# untitled.net
KiCad netlist of a schematic drawn in EAGLE
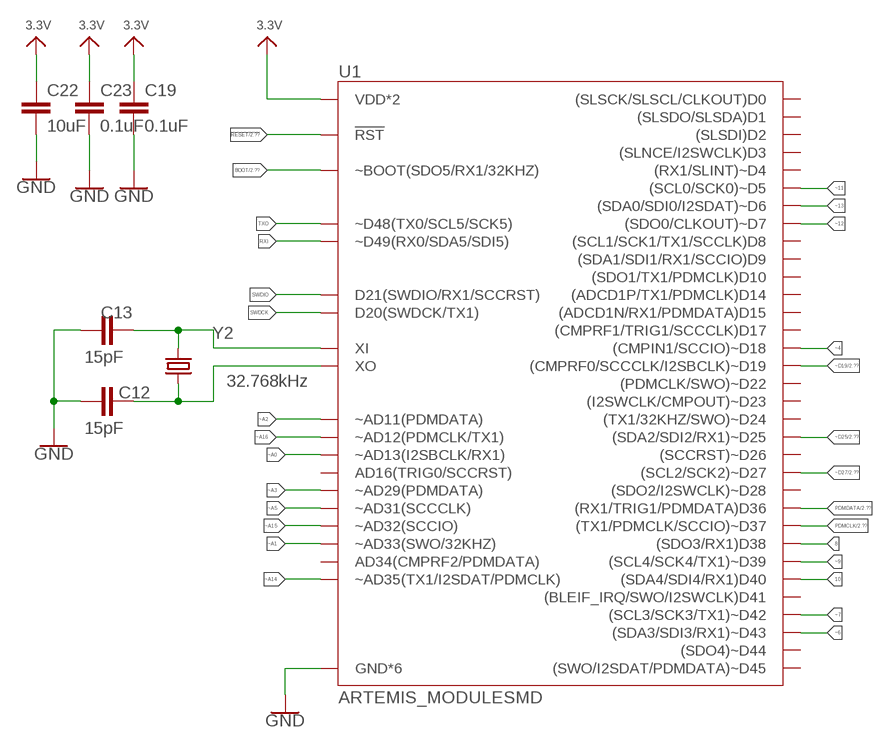
[diagram p0: schematic, sheet 1, part 1 of 2]
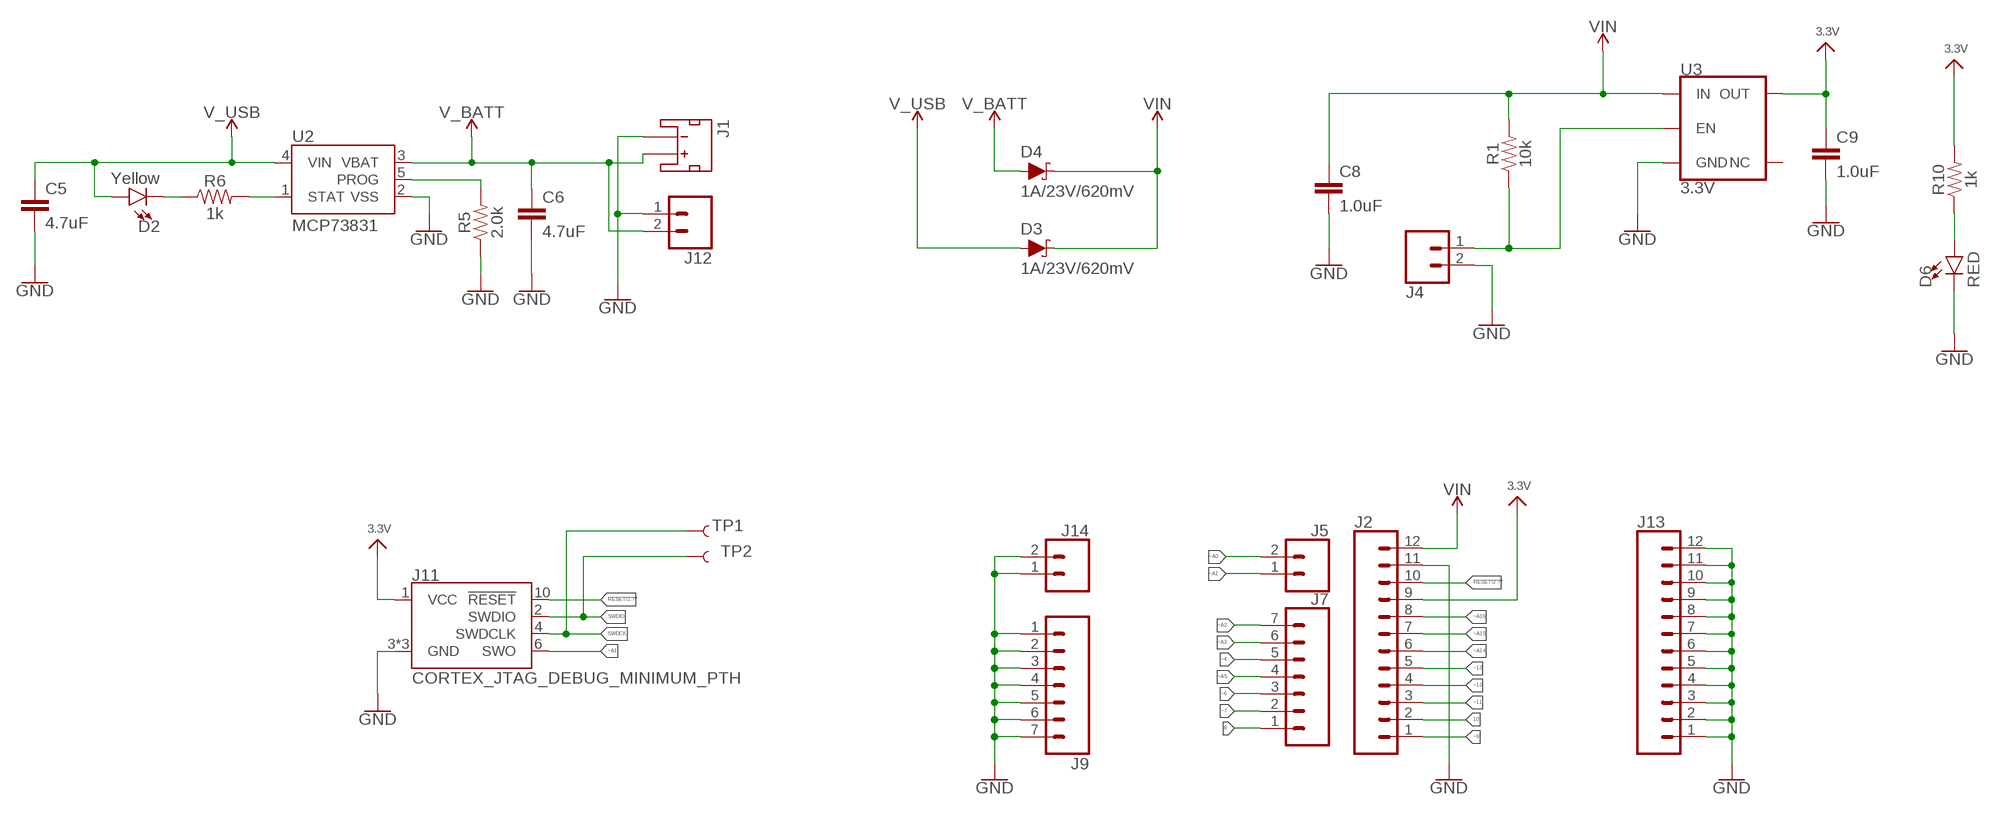
[diagram p1: schematic, sheet 1, part 2 of 2]
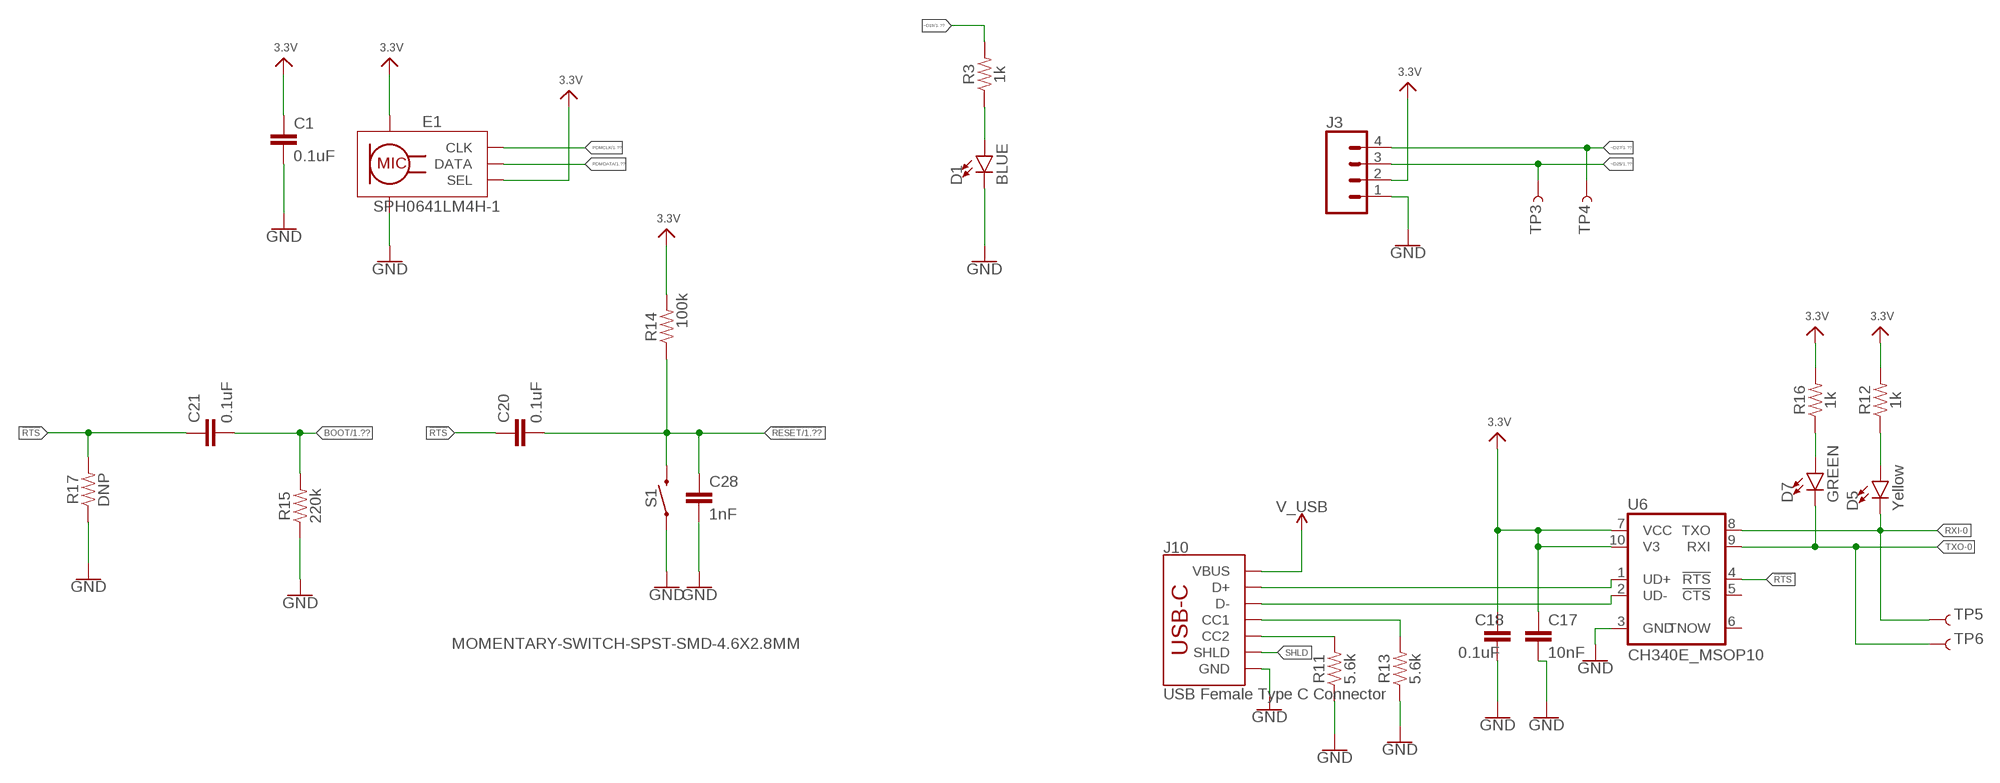
[diagram p2: schematic, sheet 2]

(export (version "E")
  (design (tool "Eeschema 10.0.6"))
  (components
    (comp (ref "C5")
      (value "4.7uF")
      (footprint "eagle-import:0603")
      (libsource (lib "eagle-import") (part "4.7UF-0603-6.3V-(10%)"))
    )
    (comp (ref "C6")
      (value "4.7uF")
      (footprint "eagle-import:0603")
      (libsource (lib "eagle-import") (part "4.7UF-0603-6.3V-(10%)"))
    )
    (comp (ref "C8")
      (value "1.0uF")
      (footprint "eagle-import:0402-TIGHT")
      (libsource (lib "eagle-import") (part "1.0UF-0402T-16V-10%"))
    )
    (comp (ref "C9")
      (value "1.0uF")
      (footprint "eagle-import:0402-TIGHT")
      (libsource (lib "eagle-import") (part "1.0UF-0402T-16V-10%"))
    )
    (comp (ref "C12")
      (value "15pF")
      (footprint "eagle-import:0603")
      (libsource (lib "eagle-import") (part "15PF-0603-50V-5%"))
    )
    (comp (ref "C13")
      (value "15pF")
      (footprint "eagle-import:0603")
      (libsource (lib "eagle-import") (part "15PF-0603-50V-5%"))
    )
    (comp (ref "C19")
      (value "0.1uF")
      (footprint "eagle-import:0402-TIGHT")
      (libsource (lib "eagle-import") (part "0.1UF-0402T-16V-10%"))
    )
    (comp (ref "C22")
      (value "10uF")
      (footprint "eagle-import:0603")
      (libsource (lib "eagle-import") (part "10UF-0603-6.3V-20%"))
    )
    (comp (ref "C23")
      (value "0.1uF")
      (footprint "eagle-import:0402-TIGHT")
      (libsource (lib "eagle-import") (part "0.1UF-0402T-16V-10%"))
    )
    (comp (ref "D2")
      (value "Yellow")
      (footprint "eagle-import:LED-0603")
      (libsource (lib "eagle-import") (part "LED-YELLOW0603"))
    )
    (comp (ref "D3")
      (value "1A/23V/620mV")
      (footprint "eagle-import:SOD-323")
      (libsource (lib "eagle-import") (part "DIODE-SCHOTTKY-BAT20J"))
    )
    (comp (ref "D4")
      (value "1A/23V/620mV")
      (footprint "eagle-import:SOD-323")
      (libsource (lib "eagle-import") (part "DIODE-SCHOTTKY-BAT20J"))
    )
    (comp (ref "D6")
      (value "RED")
      (footprint "eagle-import:LED-0603")
      (libsource (lib "eagle-import") (part "LED-RED0603"))
    )
    (comp (ref "J1")
      (value "JST_2MM_MALE")
      (footprint "eagle-import:JST-2-SMD")
      (libsource (lib "eagle-import") (part "JST_2MM_MALE"))
    )
    (comp (ref "J2")
      (value "CONN_12NO_SILK")
      (footprint "eagle-import:1X12_NO_SILK")
      (libsource (lib "eagle-import") (part "CONN_12NO_SILK"))
    )
    (comp (ref "J4")
      (value "CONN_021X02_NO_SILK")
      (footprint "eagle-import:1X02_NO_SILK")
      (libsource (lib "eagle-import") (part "CONN_021X02_NO_SILK"))
    )
    (comp (ref "J5")
      (value "CONN_021X02_NO_SILK")
      (footprint "eagle-import:1X02_NO_SILK")
      (libsource (lib "eagle-import") (part "CONN_021X02_NO_SILK"))
    )
    (comp (ref "J7")
      (value "CONN_07NO_SILK")
      (footprint "eagle-import:1X07_NO_SILK")
      (libsource (lib "eagle-import") (part "CONN_07NO_SILK"))
    )
    (comp (ref "J9")
      (value "CONN_07NO_SILK")
      (footprint "eagle-import:1X07_NO_SILK")
      (libsource (lib "eagle-import") (part "CONN_07NO_SILK"))
    )
    (comp (ref "J11")
      (value "CORTEX_JTAG_DEBUG_MINIMUM_PTH")
      (footprint "eagle-import:2X5-PTH-1.27MM")
      (libsource (lib "eagle-import") (part "CORTEX_JTAG_DEBUG_MINIMUM_PTH"))
    )
    (comp (ref "J12")
      (value "CONN_021X02_NO_SILK")
      (footprint "eagle-import:1X02_NO_SILK")
      (libsource (lib "eagle-import") (part "CONN_021X02_NO_SILK"))
    )
    (comp (ref "J13")
      (value "CONN_12NO_SILK")
      (footprint "eagle-import:1X12_NO_SILK")
      (libsource (lib "eagle-import") (part "CONN_12NO_SILK"))
    )
    (comp (ref "J14")
      (value "CONN_021X02_NO_SILK")
      (footprint "eagle-import:1X02_NO_SILK")
      (libsource (lib "eagle-import") (part "CONN_021X02_NO_SILK"))
    )
    (comp (ref "R1")
      (value "10k")
      (footprint "eagle-import:0603")
      (libsource (lib "eagle-import") (part "10KOHM-0603-1/10W-1%"))
    )
    (comp (ref "R5")
      (value "2.0k")
      (footprint "eagle-import:0603")
      (libsource (lib "eagle-import") (part "2.0KOHM-0603-1/10W-5%"))
    )
    (comp (ref "R6")
      (value "1k")
      (footprint "eagle-import:0603")
      (libsource (lib "eagle-import") (part "1KOHM-0603-1/10W-1%"))
    )
    (comp (ref "R10")
      (value "1k")
      (footprint "eagle-import:0603")
      (libsource (lib "eagle-import") (part "1KOHM-0603-1/10W-1%"))
    )
    (comp (ref "TP1")
      (value "TEST-POINT3X5")
      (footprint "eagle-import:PAD.03X.05")
      (libsource (lib "eagle-import") (part "TEST-POINT3X5"))
    )
    (comp (ref "TP2")
      (value "TEST-POINT3X5")
      (footprint "eagle-import:PAD.03X.05")
      (libsource (lib "eagle-import") (part "TEST-POINT3X5"))
    )
    (comp (ref "U1")
      (value "ARTEMIS_MODULESMD")
      (footprint "eagle-import:ARTEMIS_FP")
      (libsource (lib "eagle-import") (part "ARTEMIS_MODULESMD"))
    )
    (comp (ref "U2")
      (value "MCP73831")
      (footprint "eagle-import:SOT23-5")
      (libsource (lib "eagle-import") (part "MCP73831"))
    )
    (comp (ref "U3")
      (value "3.3V")
      (footprint "eagle-import:SOT23-5")
      (libsource (lib "eagle-import") (part "V_REG_AP2112K-3.3V"))
    )
    (comp (ref "Y2")
      (value "32.768kHz")
      (footprint "eagle-import:CRYSTAL-SMD-3.2X1.5MM")
      (libsource (lib "eagle-import") (part "CRYSTAL-32.768KHZSMD-3.2X1.5"))
    )
    (comp (ref "C1")
      (value "0.1uF")
      (footprint "eagle-import:0402-TIGHT")
      (libsource (lib "eagle-import") (part "0.1UF-0402T-16V-10%"))
    )
    (comp (ref "C17")
      (value "10nF")
      (footprint "eagle-import:0603")
      (libsource (lib "eagle-import") (part "10NF-0603-50V-10%"))
    )
    (comp (ref "C18")
      (value "0.1uF")
      (footprint "eagle-import:0603")
      (libsource (lib "eagle-import") (part "0.1UF-0603-25V-(+80/-20%)"))
    )
    (comp (ref "C20")
      (value "0.1uF")
      (footprint "eagle-import:0603")
      (libsource (lib "eagle-import") (part "0.1UF-0603-25V-5%"))
    )
    (comp (ref "C21")
      (value "0.1uF")
      (footprint "eagle-import:0603")
      (libsource (lib "eagle-import") (part "0.1UF-0603-25V-5%"))
    )
    (comp (ref "C28")
      (value "1nF")
      (footprint "eagle-import:0603")
      (libsource (lib "eagle-import") (part "1.0NF/1000PF-0603-50V-10%"))
    )
    (comp (ref "D1")
      (value "BLUE")
      (footprint "eagle-import:LED-0603")
      (libsource (lib "eagle-import") (part "LED-BLUE0603"))
    )
    (comp (ref "D5")
      (value "Yellow")
      (footprint "eagle-import:LED-0603")
      (libsource (lib "eagle-import") (part "LED-YELLOW0603"))
    )
    (comp (ref "D7")
      (value "GREEN")
      (footprint "eagle-import:LED-0603")
      (libsource (lib "eagle-import") (part "LED-GREEN0603"))
    )
    (comp (ref "E1")
      (value "SPH0641LM4H-1")
      (footprint "eagle-import:SPH0641LM4H-1_MICROPHONE")
      (libsource (lib "eagle-import") (part "SPH0641LM4H-1_MICROPHONE"))
    )
    (comp (ref "J3")
      (value "CONN_04SMD2")
      (footprint "eagle-import:JST04_1MM_RA")
      (libsource (lib "eagle-import") (part "CONN_04SMD2"))
    )
    (comp (ref "J10")
      (value "USB Female Type C Connector")
      (footprint "eagle-import:USB-C-16P-4LAYER-ISOLATED")
      (libsource (lib "eagle-import") (part "USB_C_4-LAYER-ISOLATED"))
    )
    (comp (ref "R3")
      (value "1k")
      (footprint "eagle-import:0603")
      (libsource (lib "eagle-import") (part "1KOHM-0603-1/10W-1%"))
    )
    (comp (ref "R11")
      (value "5.6k")
      (footprint "eagle-import:0603")
      (libsource (lib "eagle-import") (part "5.6KOHM-0603-1/10W-1%"))
    )
    (comp (ref "R12")
      (value "1k")
      (footprint "eagle-import:0603")
      (libsource (lib "eagle-import") (part "1KOHM-0603-1/10W-1%"))
    )
    (comp (ref "R13")
      (value "5.6k")
      (footprint "eagle-import:0603")
      (libsource (lib "eagle-import") (part "5.6KOHM-0603-1/10W-1%"))
    )
    (comp (ref "R14")
      (value "100k")
      (footprint "eagle-import:0603")
      (libsource (lib "eagle-import") (part "100KOHM-0603-1/10W-1%"))
    )
    (comp (ref "R15")
      (value "220k")
      (footprint "eagle-import:0603")
      (libsource (lib "eagle-import") (part "220KOHM-0603-1/10W-1%"))
    )
    (comp (ref "R16")
      (value "1k")
      (footprint "eagle-import:0603")
      (libsource (lib "eagle-import") (part "1KOHM-0603-1/10W-1%"))
    )
    (comp (ref "R17")
      (value "DNP")
      (footprint "eagle-import:0603")
      (libsource (lib "eagle-import") (part "DNP-0603"))
    )
    (comp (ref "S1")
      (value "MOMENTARY-SWITCH-SPST-SMD-4.6X2.8MM")
      (footprint "eagle-import:TACTILE_SWITCH_SMD_4.6X2.8MM")
      (libsource (lib "eagle-import") (part "MOMENTARY-SWITCH-SPST-SMD-4.6X2.8MM"))
    )
    (comp (ref "TP3")
      (value "TEST-POINT3X5")
      (footprint "eagle-import:PAD.03X.05")
      (libsource (lib "eagle-import") (part "TEST-POINT3X5"))
    )
    (comp (ref "TP4")
      (value "TEST-POINT3X5")
      (footprint "eagle-import:PAD.03X.05")
      (libsource (lib "eagle-import") (part "TEST-POINT3X5"))
    )
    (comp (ref "TP5")
      (value "TEST-POINT3X5")
      (footprint "eagle-import:PAD.03X.05")
      (libsource (lib "eagle-import") (part "TEST-POINT3X5"))
    )
    (comp (ref "TP6")
      (value "TEST-POINT3X5")
      (footprint "eagle-import:PAD.03X.05")
      (libsource (lib "eagle-import") (part "TEST-POINT3X5"))
    )
    (comp (ref "U6")
      (value "CH340E_MSOP10")
      (footprint "eagle-import:MSOP10")
      (libsource (lib "eagle-import") (part "CH340E_MSOP10"))
    )
  )
  (nets
    (net (code "1") (name "3.3V") (class "Default")
      (node (ref "C1") (pin "1") (pinfunction "1_1") (pintype "passive"))
      (node (ref "C17") (pin "1") (pinfunction "1_1") (pintype "passive"))
      (node (ref "C18") (pin "1") (pinfunction "1_1") (pintype "passive"))
      (node (ref "C19") (pin "1") (pinfunction "1_1") (pintype "passive"))
      (node (ref "C22") (pin "1") (pinfunction "1_1") (pintype "passive"))
      (node (ref "C23") (pin "1") (pinfunction "1_1") (pintype "passive"))
      (node (ref "C9") (pin "1") (pinfunction "1_1") (pintype "passive"))
      (node (ref "E1") (pin "2") (pinfunction "SEL_2") (pintype "input"))
      (node (ref "E1") (pin "5") (pinfunction "VDD_5") (pintype "power_in"))
      (node (ref "J11") (pin "1") (pinfunction "VCC_1") (pintype "bidirectional"))
      (node (ref "J2") (pin "9") (pinfunction "9_9") (pintype "passive"))
      (node (ref "J3") (pin "2") (pinfunction "2_2") (pintype "passive"))
      (node (ref "R10") (pin "2") (pinfunction "2_2") (pintype "passive"))
      (node (ref "R12") (pin "2") (pinfunction "2_2") (pintype "passive"))
      (node (ref "R14") (pin "2") (pinfunction "2_2") (pintype "passive"))
      (node (ref "R16") (pin "2") (pinfunction "2_2") (pintype "passive"))
      (node (ref "U1") (pin "VDD@36") (pinfunction "VDD*2_VDD@36") (pintype "bidirectional"))
      (node (ref "U1") (pin "VDD@37") (pinfunction "VDD*2_VDD@37") (pintype "bidirectional"))
      (node (ref "U3") (pin "5") (pinfunction "OUT_5") (pintype "passive"))
      (node (ref "U6") (pin "10") (pinfunction "V3_10") (pintype "bidirectional"))
      (node (ref "U6") (pin "7") (pinfunction "VCC_7") (pintype "bidirectional"))
    )
    (net (code "2") (name "8") (class "Default")
      (node (ref "J7") (pin "1") (pinfunction "1_1") (pintype "passive"))
      (node (ref "U1") (pin "D38") (pinfunction "(SDO3/RX1)D38_D38") (pintype "bidirectional"))
    )
    (net (code "3") (name "10") (class "Default")
      (node (ref "J2") (pin "2") (pinfunction "2_2") (pintype "passive"))
      (node (ref "U1") (pin "D40") (pinfunction "(SDA4/SDI4/RX1)D40_D40") (pintype "bidirectional"))
    )
    (net (code "4") (name "BOOT") (class "Default")
      (node (ref "C21") (pin "2") (pinfunction "2_2") (pintype "passive"))
      (node (ref "R15") (pin "2") (pinfunction "2_2") (pintype "passive"))
      (node (ref "U1") (pin "BOOT") (pinfunction "~{BOOT(SDO5/RX1/32KHZ})_BOOT") (pintype "bidirectional"))
    )
    (net (code "5") (name "GND") (class "Default")
      (node (ref "C1") (pin "2") (pinfunction "2_2") (pintype "passive"))
      (node (ref "C12") (pin "1") (pinfunction "1_1") (pintype "passive"))
      (node (ref "C13") (pin "1") (pinfunction "1_1") (pintype "passive"))
      (node (ref "C17") (pin "2") (pinfunction "2_2") (pintype "passive"))
      (node (ref "C18") (pin "2") (pinfunction "2_2") (pintype "passive"))
      (node (ref "C19") (pin "2") (pinfunction "2_2") (pintype "passive"))
      (node (ref "C22") (pin "2") (pinfunction "2_2") (pintype "passive"))
      (node (ref "C23") (pin "2") (pinfunction "2_2") (pintype "passive"))
      (node (ref "C28") (pin "2") (pinfunction "2_2") (pintype "passive"))
      (node (ref "C5") (pin "2") (pinfunction "2_2") (pintype "passive"))
      (node (ref "C6") (pin "2") (pinfunction "2_2") (pintype "passive"))
      (node (ref "C8") (pin "2") (pinfunction "2_2") (pintype "passive"))
      (node (ref "C9") (pin "2") (pinfunction "2_2") (pintype "passive"))
      (node (ref "D1") (pin "C") (pinfunction "C_C") (pintype "passive"))
      (node (ref "D6") (pin "C") (pinfunction "C_C") (pintype "passive"))
      (node (ref "E1") (pin "3") (pinfunction "GND_3") (pintype "power_in"))
      (node (ref "E1") (pin "6") (pinfunction "GND_6") (pintype "power_in"))
      (node (ref "E1") (pin "7") (pinfunction "GND_7") (pintype "power_in"))
      (node (ref "E1") (pin "8") (pinfunction "GND_8") (pintype "power_in"))
      (node (ref "J1") (pin "1") (pinfunction "-_1") (pintype "bidirectional"))
      (node (ref "J10") (pin "GND") (pinfunction "GND_GND") (pintype "bidirectional"))
      (node (ref "J10") (pin "GND2") (pinfunction "GND_GND2") (pintype "bidirectional"))
      (node (ref "J11") (pin "3") (pinfunction "GND_3") (pintype "bidirectional"))
      (node (ref "J11") (pin "5") (pinfunction "GND_5") (pintype "bidirectional"))
      (node (ref "J11") (pin "9") (pinfunction "GND_9") (pintype "bidirectional"))
      (node (ref "J12") (pin "1") (pinfunction "1_1") (pintype "passive"))
      (node (ref "J13") (pin "1") (pinfunction "1_1") (pintype "passive"))
      (node (ref "J13") (pin "10") (pinfunction "10_10") (pintype "passive"))
      (node (ref "J13") (pin "11") (pinfunction "11_11") (pintype "passive"))
      (node (ref "J13") (pin "12") (pinfunction "12_12") (pintype "passive"))
      (node (ref "J13") (pin "2") (pinfunction "2_2") (pintype "passive"))
      (node (ref "J13") (pin "3") (pinfunction "3_3") (pintype "passive"))
      (node (ref "J13") (pin "4") (pinfunction "4_4") (pintype "passive"))
      (node (ref "J13") (pin "5") (pinfunction "5_5") (pintype "passive"))
      (node (ref "J13") (pin "6") (pinfunction "6_6") (pintype "passive"))
      (node (ref "J13") (pin "7") (pinfunction "7_7") (pintype "passive"))
      (node (ref "J13") (pin "8") (pinfunction "8_8") (pintype "passive"))
      (node (ref "J13") (pin "9") (pinfunction "9_9") (pintype "passive"))
      (node (ref "J14") (pin "1") (pinfunction "1_1") (pintype "passive"))
      (node (ref "J14") (pin "2") (pinfunction "2_2") (pintype "passive"))
      (node (ref "J2") (pin "11") (pinfunction "11_11") (pintype "passive"))
      (node (ref "J3") (pin "1") (pinfunction "1_1") (pintype "passive"))
      (node (ref "J4") (pin "2") (pinfunction "2_2") (pintype "passive"))
      (node (ref "J9") (pin "1") (pinfunction "1_1") (pintype "passive"))
      (node (ref "J9") (pin "2") (pinfunction "2_2") (pintype "passive"))
      (node (ref "J9") (pin "3") (pinfunction "3_3") (pintype "passive"))
      (node (ref "J9") (pin "4") (pinfunction "4_4") (pintype "passive"))
      (node (ref "J9") (pin "5") (pinfunction "5_5") (pintype "passive"))
      (node (ref "J9") (pin "6") (pinfunction "6_6") (pintype "passive"))
      (node (ref "J9") (pin "7") (pinfunction "7_7") (pintype "passive"))
      (node (ref "R11") (pin "1") (pinfunction "1_1") (pintype "passive"))
      (node (ref "R13") (pin "1") (pinfunction "1_1") (pintype "passive"))
      (node (ref "R15") (pin "1") (pinfunction "1_1") (pintype "passive"))
      (node (ref "R17") (pin "1") (pinfunction "1_1") (pintype "passive"))
      (node (ref "R5") (pin "1") (pinfunction "1_1") (pintype "passive"))
      (node (ref "S1") (pin "1") (pinfunction "1_1") (pintype "passive"))
      (node (ref "S1") (pin "2") (pinfunction "1_2") (pintype "passive"))
      (node (ref "U1") (pin "GND@1") (pinfunction "GND*6_GND@1") (pintype "bidirectional"))
      (node (ref "U1") (pin "GND@22") (pinfunction "GND*6_GND@22") (pintype "bidirectional"))
      (node (ref "U1") (pin "GND@38") (pinfunction "GND*6_GND@38") (pintype "bidirectional"))
      (node (ref "U1") (pin "GND@39") (pinfunction "GND*6_GND@39") (pintype "bidirectional"))
      (node (ref "U1") (pin "GND@47") (pinfunction "GND*6_GND@47") (pintype "bidirectional"))
      (node (ref "U1") (pin "GND@59") (pinfunction "GND*6_GND@59") (pintype "bidirectional"))
      (node (ref "U2") (pin "2") (pinfunction "VSS_2") (pintype "power_in"))
      (node (ref "U3") (pin "2") (pinfunction "GND_2") (pintype "input"))
      (node (ref "U6") (pin "3") (pinfunction "GND_3") (pintype "bidirectional"))
    )
    (net (code "6") (name "Net-(D1-PadA)") (class "Default")
      (node (ref "D1") (pin "A") (pinfunction "A_A") (pintype "passive"))
      (node (ref "R3") (pin "1") (pinfunction "1_1") (pintype "passive"))
    )
    (net (code "7") (name "Net-(D2-PadC)") (class "Default")
      (node (ref "D2") (pin "C") (pinfunction "C_C") (pintype "passive"))
      (node (ref "R6") (pin "1") (pinfunction "1_1") (pintype "passive"))
    )
    (net (code "8") (name "Net-(D5-PadA)") (class "Default")
      (node (ref "D5") (pin "A") (pinfunction "A_A") (pintype "passive"))
      (node (ref "R12") (pin "1") (pinfunction "1_1") (pintype "passive"))
    )
    (net (code "9") (name "Net-(D6-PadA)") (class "Default")
      (node (ref "D6") (pin "A") (pinfunction "A_A") (pintype "passive"))
      (node (ref "R10") (pin "1") (pinfunction "1_1") (pintype "passive"))
    )
    (net (code "10") (name "Net-(D7-PadA)") (class "Default")
      (node (ref "D7") (pin "A") (pinfunction "A_A") (pintype "passive"))
      (node (ref "R16") (pin "1") (pinfunction "1_1") (pintype "passive"))
    )
    (net (code "11") (name "Net-(J10-CC1)") (class "Default")
      (node (ref "J10") (pin "A5") (pinfunction "CC1_A5") (pintype "bidirectional"))
      (node (ref "R13") (pin "2") (pinfunction "2_2") (pintype "passive"))
    )
    (net (code "12") (name "Net-(J10-CC2)") (class "Default")
      (node (ref "J10") (pin "B5") (pinfunction "CC2_B5") (pintype "bidirectional"))
      (node (ref "R11") (pin "2") (pinfunction "2_2") (pintype "passive"))
    )
    (net (code "13") (name "Net-(U2-PROG)") (class "Default")
      (node (ref "R5") (pin "2") (pinfunction "2_2") (pintype "passive"))
      (node (ref "U2") (pin "5") (pinfunction "PROG_5") (pintype "input"))
    )
    (net (code "14") (name "Net-(U2-STAT)") (class "Default")
      (node (ref "R6") (pin "2") (pinfunction "2_2") (pintype "passive"))
      (node (ref "U2") (pin "1") (pinfunction "STAT_1") (pintype "output"))
    )
    (net (code "15") (name "Net-(U3-EN)") (class "Default")
      (node (ref "J4") (pin "1") (pinfunction "1_1") (pintype "passive"))
      (node (ref "R1") (pin "1") (pinfunction "1_1") (pintype "passive"))
      (node (ref "U3") (pin "3") (pinfunction "EN_3") (pintype "input"))
    )
    (net (code "16") (name "Net-(U6-UD+)") (class "Default")
      (node (ref "J10") (pin "A6") (pinfunction "D+_A6") (pintype "bidirectional"))
      (node (ref "J10") (pin "B6") (pinfunction "D+_B6") (pintype "bidirectional"))
      (node (ref "U6") (pin "1") (pinfunction "UD+_1") (pintype "bidirectional"))
    )
    (net (code "17") (name "Net-(U6-UD-)") (class "Default")
      (node (ref "J10") (pin "A7") (pinfunction "D-_A7") (pintype "bidirectional"))
      (node (ref "J10") (pin "B7") (pinfunction "D-_B7") (pintype "bidirectional"))
      (node (ref "U6") (pin "2") (pinfunction "UD-_2") (pintype "bidirectional"))
    )
    (net (code "18") (name "Net-(Y2-1)") (class "Default")
      (node (ref "C12") (pin "2") (pinfunction "2_2") (pintype "passive"))
      (node (ref "U1") (pin "XO") (pinfunction "XO_XO") (pintype "bidirectional"))
      (node (ref "Y2") (pin "P$1") (pinfunction "1_P$1") (pintype "passive"))
    )
    (net (code "19") (name "Net-(Y2-2)") (class "Default")
      (node (ref "C13") (pin "2") (pinfunction "2_2") (pintype "passive"))
      (node (ref "U1") (pin "XI") (pinfunction "XI_XI") (pintype "bidirectional"))
      (node (ref "Y2") (pin "P$2") (pinfunction "2_P$2") (pintype "passive"))
    )
    (net (code "20") (name "PDMCLK") (class "Default")
      (node (ref "E1") (pin "4") (pinfunction "CLK_4") (pintype "input"))
      (node (ref "U1") (pin "~D37") (pinfunction "(TX1/PDMCLK/SCCIO)~{D37}_~D37") (pintype "bidirectional"))
    )
    (net (code "21") (name "PDMDATA") (class "Default")
      (node (ref "E1") (pin "1") (pinfunction "DATA_1") (pintype "output"))
      (node (ref "U1") (pin "D36") (pinfunction "(RX1/TRIG1/PDMDATA)D36_D36") (pintype "bidirectional"))
    )
    (net (code "22") (name "RXI") (class "Default")
      (node (ref "U1") (pin "RXI-0") (pinfunction "~{D49(RX0/SDA5/SDI5})_RXI-0") (pintype "bidirectional"))
    )
    (net (code "23") (name "RXI-0") (class "Default")
      (node (ref "D5") (pin "C") (pinfunction "C_C") (pintype "passive"))
      (node (ref "TP5") (pin "1") (pinfunction "1_1") (pintype "bidirectional"))
      (node (ref "U6") (pin "8") (pinfunction "TXO_8") (pintype "bidirectional"))
    )
    (net (code "24") (name "SHLD") (class "Default")
      (node (ref "J10") (pin "SHLD1") (pinfunction "SHLD_SHLD1") (pintype "bidirectional"))
      (node (ref "J10") (pin "SHLD2") (pinfunction "SHLD_SHLD2") (pintype "bidirectional"))
      (node (ref "J10") (pin "SHLD3") (pinfunction "SHLD_SHLD3") (pintype "bidirectional"))
      (node (ref "J10") (pin "SHLD4") (pinfunction "SHLD_SHLD4") (pintype "bidirectional"))
      (node (ref "J10") (pin "SHLD5") (pinfunction "SHLD_SHLD5") (pintype "bidirectional"))
      (node (ref "J10") (pin "SHLD6") (pinfunction "SHLD_SHLD6") (pintype "bidirectional"))
      (node (ref "J10") (pin "SHLD7") (pinfunction "SHLD_SHLD7") (pintype "bidirectional"))
      (node (ref "J10") (pin "SHLD8") (pinfunction "SHLD_SHLD8") (pintype "bidirectional"))
    )
    (net (code "25") (name "SWDCK") (class "Default")
      (node (ref "J11") (pin "4") (pinfunction "SWDCLK_4") (pintype "bidirectional"))
      (node (ref "TP1") (pin "1") (pinfunction "1_1") (pintype "bidirectional"))
      (node (ref "U1") (pin "SWDCK") (pinfunction "D20(SWDCK/TX1)_SWDCK") (pintype "bidirectional"))
    )
    (net (code "26") (name "SWDIO") (class "Default")
      (node (ref "J11") (pin "2") (pinfunction "SWDIO_2") (pintype "bidirectional"))
      (node (ref "TP2") (pin "1") (pinfunction "1_1") (pintype "bidirectional"))
      (node (ref "U1") (pin "SWDIO") (pinfunction "D21(SWDIO/RX1/SCCRST)_SWDIO") (pintype "bidirectional"))
    )
    (net (code "27") (name "TXO") (class "Default")
      (node (ref "U1") (pin "TXO-0") (pinfunction "~{D48(TX0/SCL5/SCK5})_TXO-0") (pintype "bidirectional"))
    )
    (net (code "28") (name "TXO-0") (class "Default")
      (node (ref "D7") (pin "C") (pinfunction "C_C") (pintype "passive"))
      (node (ref "TP6") (pin "1") (pinfunction "1_1") (pintype "bidirectional"))
      (node (ref "U6") (pin "9") (pinfunction "RXI_9") (pintype "bidirectional"))
    )
    (net (code "29") (name "VIN") (class "Default")
      (node (ref "C8") (pin "1") (pinfunction "1_1") (pintype "passive"))
      (node (ref "D3") (pin "C") (pinfunction "C_C") (pintype "passive"))
      (node (ref "D4") (pin "C") (pinfunction "C_C") (pintype "passive"))
      (node (ref "J2") (pin "12") (pinfunction "12_12") (pintype "passive"))
      (node (ref "R1") (pin "2") (pinfunction "2_2") (pintype "passive"))
      (node (ref "U3") (pin "1") (pinfunction "IN_1") (pintype "input"))
    )
    (net (code "30") (name "V_BATT") (class "Default")
      (node (ref "C6") (pin "1") (pinfunction "1_1") (pintype "passive"))
      (node (ref "D4") (pin "A") (pinfunction "A_A") (pintype "passive"))
      (node (ref "J1") (pin "2") (pinfunction "+_2") (pintype "bidirectional"))
      (node (ref "J12") (pin "2") (pinfunction "2_2") (pintype "passive"))
      (node (ref "U2") (pin "3") (pinfunction "VBAT_3") (pintype "power_in"))
    )
    (net (code "31") (name "V_USB") (class "Default")
      (node (ref "C5") (pin "1") (pinfunction "1_1") (pintype "passive"))
      (node (ref "D2") (pin "A") (pinfunction "A_A") (pintype "passive"))
      (node (ref "D3") (pin "A") (pinfunction "A_A") (pintype "passive"))
      (node (ref "J10") (pin "VBUS1") (pinfunction "VBUS_VBUS1") (pintype "bidirectional"))
      (node (ref "J10") (pin "VBUS2") (pinfunction "VBUS_VBUS2") (pintype "bidirectional"))
      (node (ref "U2") (pin "4") (pinfunction "VIN_4") (pintype "power_in"))
    )
    (net (code "32") (name "unconnected-(J1-PAD1-PadNC1)") (class "Default")
      (node (ref "J1") (pin "NC1") (pinfunction "PAD1_NC1") (pintype "bidirectional"))
    )
    (net (code "33") (name "unconnected-(J1-PAD2-PadNC2)") (class "Default")
      (node (ref "J1") (pin "NC2") (pinfunction "PAD2_NC2") (pintype "bidirectional"))
    )
    (net (code "34") (name "unconnected-(U1-(ADCD1N{slash}RX1{slash}PDMDATA)D15-PadD15)") (class "Default")
      (node (ref "U1") (pin "D15") (pinfunction "(ADCD1N/RX1/PDMDATA)D15_D15") (pintype "bidirectional"))
    )
    (net (code "35") (name "unconnected-(U1-(ADCD1P{slash}TX1{slash}PDMCLK)D14-PadD14)") (class "Default")
      (node (ref "U1") (pin "D14") (pinfunction "(ADCD1P/TX1/PDMCLK)D14_D14") (pintype "bidirectional"))
    )
    (net (code "36") (name "unconnected-(U1-(BLEIF_IRQ{slash}SWO{slash}I2SWCLK)D41-PadD41)") (class "Default")
      (node (ref "U1") (pin "D41") (pinfunction "(BLEIF_IRQ/SWO/I2SWCLK)D41_D41") (pintype "bidirectional"))
    )
    (net (code "37") (name "unconnected-(U1-(CMPRF1{slash}TRIG1{slash}SCCCLK)D17-PadD17)") (class "Default")
      (node (ref "U1") (pin "D17") (pinfunction "(CMPRF1/TRIG1/SCCCLK)D17_D17") (pintype "bidirectional"))
    )
    (net (code "38") (name "unconnected-(U1-(I2SWCLK{slash}CMPOUT)~{D23}-Pad~D23)") (class "Default")
      (node (ref "U1") (pin "~D23") (pinfunction "(I2SWCLK/CMPOUT)~{D23}_~D23") (pintype "bidirectional"))
    )
    (net (code "39") (name "unconnected-(U1-(PDMCLK{slash}SWO)~{D22}-Pad~D22)") (class "Default")
      (node (ref "U1") (pin "~D22") (pinfunction "(PDMCLK/SWO)~{D22}_~D22") (pintype "bidirectional"))
    )
    (net (code "40") (name "unconnected-(U1-(RX1{slash}SLINT)~{D4}-Pad~D4)") (class "Default")
      (node (ref "U1") (pin "~D4") (pinfunction "(RX1/SLINT)~{D4}_~D4") (pintype "bidirectional"))
    )
    (net (code "41") (name "unconnected-(U1-(SCCRST)~{D26}-Pad~D26)") (class "Default")
      (node (ref "U1") (pin "~D26") (pinfunction "(SCCRST)~{D26}_~D26") (pintype "bidirectional"))
    )
    (net (code "42") (name "unconnected-(U1-(SCL1{slash}SCK1{slash}TX1{slash}SCCLK)D8-PadD8)") (class "Default")
      (node (ref "U1") (pin "D8") (pinfunction "(SCL1/SCK1/TX1/SCCLK)D8_D8") (pintype "bidirectional"))
    )
    (net (code "43") (name "unconnected-(U1-(SDA1{slash}SDI1{slash}RX1{slash}SCCIO)D9-PadD9)") (class "Default")
      (node (ref "U1") (pin "D9") (pinfunction "(SDA1/SDI1/RX1/SCCIO)D9_D9") (pintype "bidirectional"))
    )
    (net (code "44") (name "unconnected-(U1-(SDO1{slash}TX1{slash}PDMCLK)D10-PadD10)") (class "Default")
      (node (ref "U1") (pin "D10") (pinfunction "(SDO1/TX1/PDMCLK)D10_D10") (pintype "bidirectional"))
    )
    (net (code "45") (name "unconnected-(U1-(SDO2{slash}I2SWCLK)~{D28}-Pad~D28)") (class "Default")
      (node (ref "U1") (pin "~D28") (pinfunction "(SDO2/I2SWCLK)~{D28}_~D28") (pintype "bidirectional"))
    )
    (net (code "46") (name "unconnected-(U1-(SDO4)~{D44}-Pad~D44)") (class "Default")
      (node (ref "U1") (pin "~D44") (pinfunction "(SDO4)~{D44}_~D44") (pintype "bidirectional"))
    )
    (net (code "47") (name "unconnected-(U1-(SLNCE{slash}I2SWCLK)D3-PadD3)") (class "Default")
      (node (ref "U1") (pin "D3") (pinfunction "(SLNCE/I2SWCLK)D3_D3") (pintype "bidirectional"))
    )
    (net (code "48") (name "unconnected-(U1-(SLSCK{slash}SLSCL{slash}CLKOUT)D0-PadD0)") (class "Default")
      (node (ref "U1") (pin "D0") (pinfunction "(SLSCK/SLSCL/CLKOUT)D0_D0") (pintype "bidirectional"))
    )
    (net (code "49") (name "unconnected-(U1-(SLSDI)D2-PadD2)") (class "Default")
      (node (ref "U1") (pin "D2") (pinfunction "(SLSDI)D2_D2") (pintype "bidirectional"))
    )
    (net (code "50") (name "unconnected-(U1-(SLSDO{slash}SLSDA)D1-PadD1)") (class "Default")
      (node (ref "U1") (pin "D1") (pinfunction "(SLSDO/SLSDA)D1_D1") (pintype "bidirectional"))
    )
    (net (code "51") (name "unconnected-(U1-(SWO{slash}I2SDAT{slash}PDMDATA)~{D45}-Pad~D45)") (class "Default")
      (node (ref "U1") (pin "~D45") (pinfunction "(SWO/I2SDAT/PDMDATA)~{D45}_~D45") (pintype "bidirectional"))
    )
    (net (code "52") (name "unconnected-(U1-(TX1{slash}32KHZ{slash}SWO)~{D24}-Pad~D24)") (class "Default")
      (node (ref "U1") (pin "~D24") (pinfunction "(TX1/32KHZ/SWO)~{D24}_~D24") (pintype "bidirectional"))
    )
    (net (code "53") (name "unconnected-(U1-AD16(TRIG0{slash}SCCRST)-PadAD16)") (class "Default")
      (node (ref "U1") (pin "AD16") (pinfunction "AD16(TRIG0/SCCRST)_AD16") (pintype "bidirectional"))
    )
    (net (code "54") (name "unconnected-(U1-AD34(CMPRF2{slash}PDMDATA)-PadAD34)") (class "Default")
      (node (ref "U1") (pin "AD34") (pinfunction "AD34(CMPRF2/PDMDATA)_AD34") (pintype "bidirectional"))
    )
    (net (code "55") (name "unconnected-(U3-NC-Pad4)") (class "Default")
      (node (ref "U3") (pin "4") (pinfunction "NC_4") (pintype "no_connect"))
    )
    (net (code "56") (name "unconnected-(U6-TNOW-Pad6)") (class "Default")
      (node (ref "U6") (pin "6") (pinfunction "TNOW_6") (pintype "bidirectional"))
    )
    (net (code "57") (name "unconnected-(U6-~{CTS}-Pad5)") (class "Default")
      (node (ref "U6") (pin "5") (pinfunction "~{CTS}_5") (pintype "bidirectional"))
    )
    (net (code "58") (name "~{4}") (class "Default")
      (node (ref "J7") (pin "5") (pinfunction "5_5") (pintype "passive"))
      (node (ref "U1") (pin "~D18") (pinfunction "(CMPIN1/SCCIO)~{D18}_~D18") (pintype "bidirectional"))
    )
    (net (code "59") (name "~{6}") (class "Default")
      (node (ref "J7") (pin "3") (pinfunction "3_3") (pintype "passive"))
      (node (ref "U1") (pin "~D43") (pinfunction "(SDA3/SDI3/RX1)~{D43}_~D43") (pintype "bidirectional"))
    )
    (net (code "60") (name "~{7}") (class "Default")
      (node (ref "J7") (pin "2") (pinfunction "2_2") (pintype "passive"))
      (node (ref "U1") (pin "~D42") (pinfunction "(SCL3/SCK3/TX1)~{D42}_~D42") (pintype "bidirectional"))
    )
    (net (code "61") (name "~{9}") (class "Default")
      (node (ref "J2") (pin "1") (pinfunction "1_1") (pintype "passive"))
      (node (ref "U1") (pin "~D39") (pinfunction "(SCL4/SCK4/TX1)~{D39}_~D39") (pintype "bidirectional"))
    )
    (net (code "62") (name "~{11}") (class "Default")
      (node (ref "J2") (pin "3") (pinfunction "3_3") (pintype "passive"))
      (node (ref "U1") (pin "~D5") (pinfunction "(SCL0/SCK0)~{D5}_~D5") (pintype "bidirectional"))
    )
    (net (code "63") (name "~{12}") (class "Default")
      (node (ref "J2") (pin "4") (pinfunction "4_4") (pintype "passive"))
      (node (ref "U1") (pin "D7") (pinfunction "(SDO0/CLKOUT)~{D7}_D7") (pintype "bidirectional"))
    )
    (net (code "64") (name "~{13}") (class "Default")
      (node (ref "J2") (pin "5") (pinfunction "5_5") (pintype "passive"))
      (node (ref "U1") (pin "~D6") (pinfunction "(SDA0/SDI0/I2SDAT)~{D6}_~D6") (pintype "bidirectional"))
    )
    (net (code "65") (name "~{A0}") (class "Default")
      (node (ref "J5") (pin "2") (pinfunction "2_2") (pintype "passive"))
      (node (ref "U1") (pin "~AD13") (pinfunction "~{AD13(I2SBCLK/RX1})_~AD13") (pintype "bidirectional"))
    )
    (net (code "66") (name "~{A1}") (class "Default")
      (node (ref "J11") (pin "6") (pinfunction "SWO_6") (pintype "bidirectional"))
      (node (ref "J5") (pin "1") (pinfunction "1_1") (pintype "passive"))
      (node (ref "U1") (pin "~AD33/SWO") (pinfunction "~{AD33(SWO/32KHZ})_~AD33/SWO") (pintype "bidirectional"))
    )
    (net (code "67") (name "~{A2}") (class "Default")
      (node (ref "J7") (pin "7") (pinfunction "7_7") (pintype "passive"))
      (node (ref "U1") (pin "~AD11") (pinfunction "~{AD11(PDMDATA})_~AD11") (pintype "bidirectional"))
    )
    (net (code "68") (name "~{A3}") (class "Default")
      (node (ref "J7") (pin "6") (pinfunction "6_6") (pintype "passive"))
      (node (ref "U1") (pin "~AD29") (pinfunction "~{AD29(PDMDATA})_~AD29") (pintype "bidirectional"))
    )
    (net (code "69") (name "~{A5}") (class "Default")
      (node (ref "J7") (pin "4") (pinfunction "4_4") (pintype "passive"))
      (node (ref "U1") (pin "~AD31") (pinfunction "~{AD31(SCCCLK})_~AD31") (pintype "bidirectional"))
    )
    (net (code "70") (name "~{A14}") (class "Default")
      (node (ref "J2") (pin "6") (pinfunction "6_6") (pintype "passive"))
      (node (ref "U1") (pin "~AD35") (pinfunction "~{AD35(TX1/I2SDAT/PDMCLK})_~AD35") (pintype "bidirectional"))
    )
    (net (code "71") (name "~{A15}") (class "Default")
      (node (ref "J2") (pin "7") (pinfunction "7_7") (pintype "passive"))
      (node (ref "U1") (pin "~AD32") (pinfunction "~{AD32(SCCIO})_~AD32") (pintype "bidirectional"))
    )
    (net (code "72") (name "~{A16}") (class "Default")
      (node (ref "J2") (pin "8") (pinfunction "8_8") (pintype "passive"))
      (node (ref "U1") (pin "~AD12") (pinfunction "~{AD12(PDMCLK/TX1})_~AD12") (pintype "bidirectional"))
    )
    (net (code "73") (name "~{D19}") (class "Default")
      (node (ref "R3") (pin "2") (pinfunction "2_2") (pintype "passive"))
      (node (ref "U1") (pin "~D19") (pinfunction "(CMPRF0/SCCCLK/I2SBCLK)~{D19}_~D19") (pintype "bidirectional"))
    )
    (net (code "74") (name "~{D25}") (class "Default")
      (node (ref "J3") (pin "3") (pinfunction "3_3") (pintype "passive"))
      (node (ref "TP3") (pin "1") (pinfunction "1_1") (pintype "bidirectional"))
      (node (ref "U1") (pin "~D25") (pinfunction "(SDA2/SDI2/RX1)~{D25}_~D25") (pintype "bidirectional"))
    )
    (net (code "75") (name "~{D27}") (class "Default")
      (node (ref "J3") (pin "4") (pinfunction "4_4") (pintype "passive"))
      (node (ref "TP4") (pin "1") (pinfunction "1_1") (pintype "bidirectional"))
      (node (ref "U1") (pin "~D27") (pinfunction "(SCL2/SCK2)~{D27}_~D27") (pintype "bidirectional"))
    )
    (net (code "76") (name "~{RESET}") (class "Default")
      (node (ref "C20") (pin "2") (pinfunction "2_2") (pintype "passive"))
      (node (ref "C28") (pin "1") (pinfunction "1_1") (pintype "passive"))
      (node (ref "J11") (pin "10") (pinfunction "~{RESET}_10") (pintype "bidirectional"))
      (node (ref "J2") (pin "10") (pinfunction "10_10") (pintype "passive"))
      (node (ref "R14") (pin "1") (pinfunction "1_1") (pintype "passive"))
      (node (ref "S1") (pin "3") (pinfunction "2_3") (pintype "passive"))
      (node (ref "S1") (pin "4") (pinfunction "2_4") (pintype "passive"))
      (node (ref "U1") (pin "~RST") (pinfunction "~{RST}_~RST") (pintype "bidirectional"))
    )
    (net (code "77") (name "~{RTS}") (class "Default")
      (node (ref "C20") (pin "1") (pinfunction "1_1") (pintype "passive"))
      (node (ref "C21") (pin "1") (pinfunction "1_1") (pintype "passive"))
      (node (ref "R17") (pin "2") (pinfunction "2_2") (pintype "passive"))
      (node (ref "U6") (pin "4") (pinfunction "~{RTS}_4") (pintype "bidirectional"))
    )
  )
)
